# design.net
KiCad netlist of a schematic drawn in EasyEDA Pro
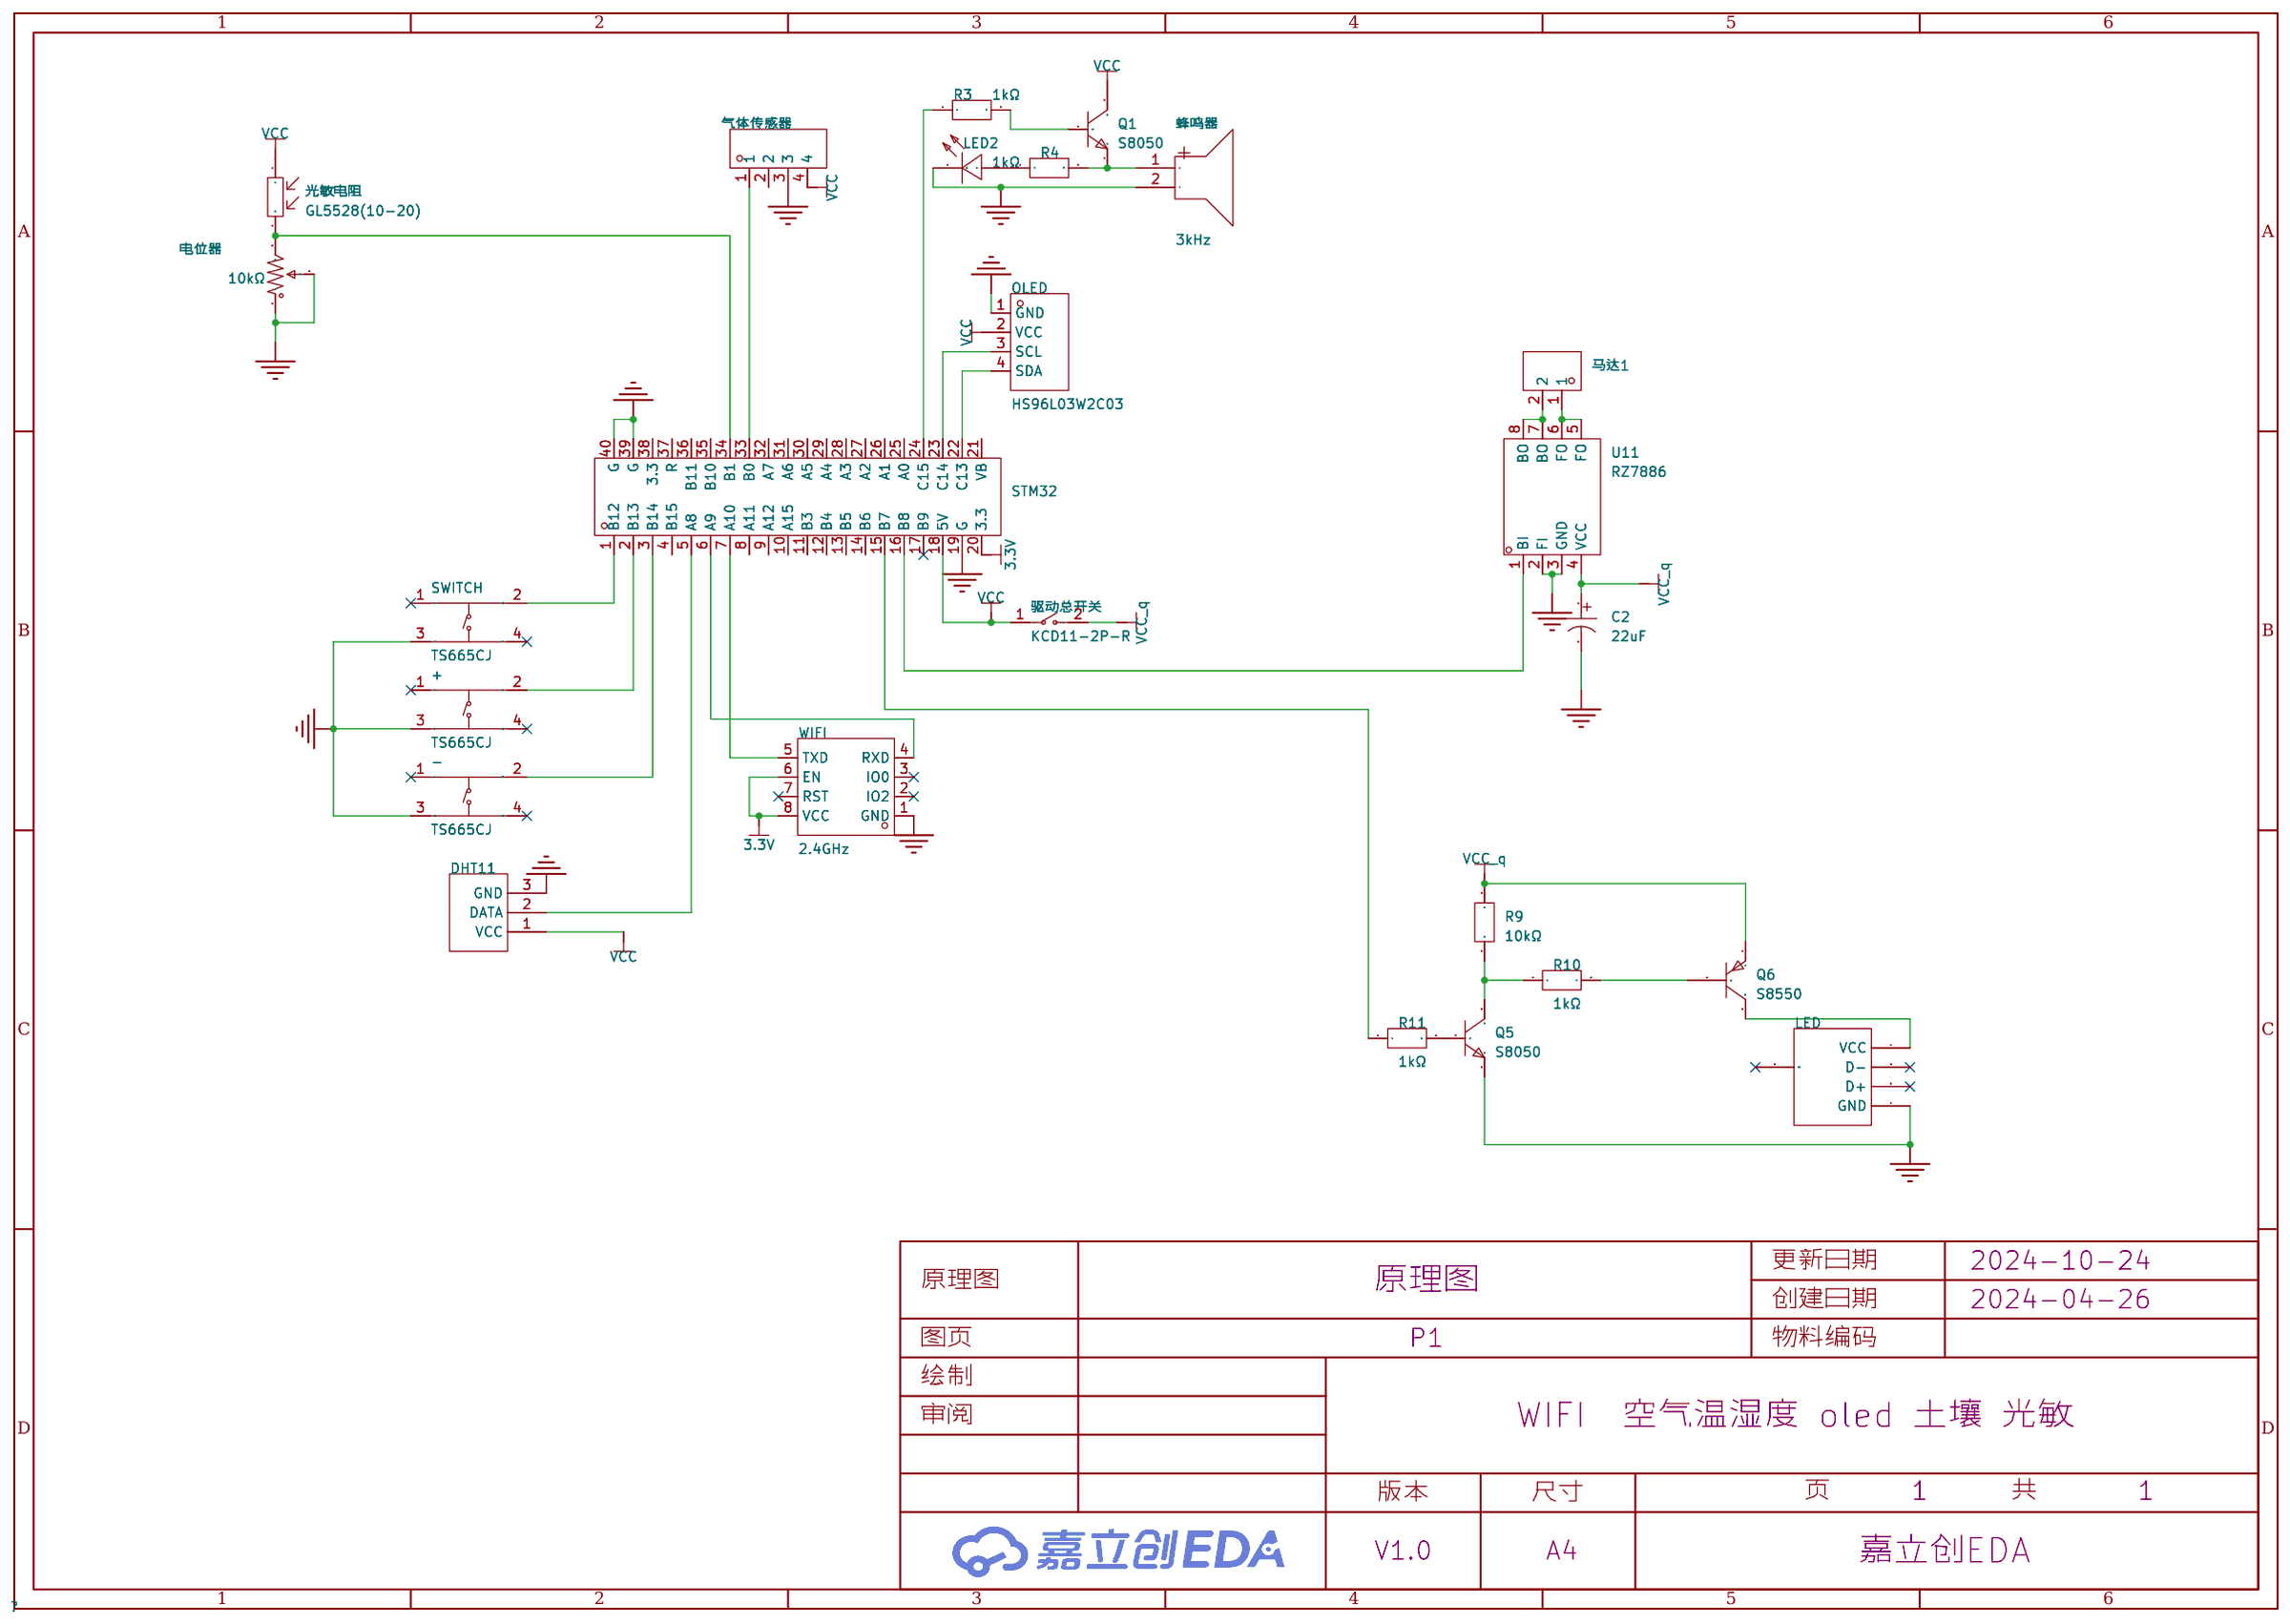
[diagram p0: schematic sheet]

(export (version "E")
  (design (tool "Eeschema 10.0.6"))
  (components
    (comp (ref "+")
      (value "TS665CJ")
      (footprint "easyedapro:SW-TH_4P-L6.0-W6.0-P4.50-LS6.5")
      (description "电路结构:单刀单掷;按钮形状:圆形按钮;安装方式:直插;开关长度:6mm;开关宽度:6mm;开关高度:5mm;触点电流:50mA;额定电压(DC):12V;带灯:-;机械寿命:-;")
      (fields (field (name "Manufacturer") "SHOU HAN(首韩)"))
      (libsource (lib "easyedapro") (part "TS665CJ"))
    )
    (comp (ref "-")
      (value "TS665CJ")
      (footprint "easyedapro:SW-TH_4P-L6.0-W6.0-P4.50-LS6.5")
      (description "电路结构:单刀单掷;按钮形状:圆形按钮;安装方式:直插;开关长度:6mm;开关宽度:6mm;开关高度:5mm;触点电流:50mA;额定电压(DC):12V;带灯:-;机械寿命:-;")
      (fields (field (name "Manufacturer") "SHOU HAN(首韩)"))
      (libsource (lib "easyedapro") (part "TS665CJ"))
    )
    (comp (ref "C2")
      (value "22uF")
      (footprint "easyedapro:CAP-TH_BD5.0-P2.00-D0.8-FD")
      (description "容值:22uF;精度:±20%;额定电压:50V;")
      (fields (field (name "Manufacturer Part") "KM220M050C110A") (field (name "Manufacturer") "CapXon(丰宾)"))
      (libsource (lib "easyedapro") (part "KM220M050C110A"))
    )
    (comp (ref "DHT11")
      (value "~")
      (footprint "easyedapro:HDR-M-2.54_1X3")
      (libsource (lib "easyedapro") (part "dht11模块"))
    )
    (comp (ref "LED")
      (value "AF 90° WJDG")
      (footprint "easyedapro:USB-A-TH_AF-WJDG")
      (description "连接器类型:Type-A;标准:USB 2.0;公母:母;端口数量:1;触点数量:4P;安装方式:弯插;额定电流 - 电源:1.5A;工作温度范围:-25°C~+85°C;")
      (fields (field (name "Manufacturer") "SHOU HAN(首韩)"))
      (libsource (lib "easyedapro") (part "AF 90° WJDG"))
    )
    (comp (ref "LED2")
      (value "204-10SDRD/S530-A3/F182-68")
      (footprint "easyedapro:LED-TH_BD4.0-P2.50-RD")
      (fields (field (name "Manufacturer") "EVERLIGHT(亿光)"))
      (libsource (lib "easyedapro") (part "204-10SDRD/S530-A3/F182-68"))
    )
    (comp (ref "OLED")
      (value "HS96L03W2C03")
      (footprint "easyedapro:OLED-TH_L27.8-W27.2-P2.54_C9900033791")
      (description "主控芯片:SSD1315;接口类型:I2C;尺寸(inch):0.96;像素分辨率:128x64;")
      (fields (field (name "Manufacturer") "HS(汉昇)"))
      (libsource (lib "easyedapro") (part "HS96L03W2C03"))
    )
    (comp (ref "Q1")
      (value "S8050")
      (footprint "easyedapro:TO-92-3_L4.5-W3.5-P1.27-L")
      (description "晶体管类型:NPN;集电极电流(Ic):500mA;集射极击穿电压(Vceo):25V;功率(Pd):625mW;直流电流增益(hFE@Ic,Vce):160@50mA,1V;")
      (fields (field (name "Manufacturer") "JSMSEMI(杰盛微)"))
      (libsource (lib "easyedapro") (part "S8050_C2931492"))
    )
    (comp (ref "Q5")
      (value "S8050")
      (footprint "easyedapro:TO-92-3_L4.5-W3.5-P1.27-L")
      (description "晶体管类型:NPN;集电极电流(Ic):500mA;集射极击穿电压(Vceo):25V;功率(Pd):625mW;直流电流增益(hFE@Ic,Vce):160@50mA,1V;")
      (fields (field (name "Manufacturer") "JSMSEMI(杰盛微)"))
      (libsource (lib "easyedapro") (part "S8050_C2931492"))
    )
    (comp (ref "Q6")
      (value "S8550")
      (footprint "easyedapro:TO-92-3_L4.5-W3.5-P1.27-L")
      (description "晶体管类型:PNP;集电极电流(Ic):500mA;集射极击穿电压(Vceo):25V;功率(Pd):625mW;直流电流增益(hFE@Ic,Vce):160@50mA,1V;")
      (fields (field (name "Manufacturer") "JSMSEMI(杰盛微)"))
      (libsource (lib "easyedapro") (part "s8550_c2931493"))
    )
    (comp (ref "R3")
      (value "1kΩ")
      (footprint "easyedapro:RES-TH_BD2.3-L6.5-P10.50-D0.5")
      (description "电阻类型:金属膜电阻;阻值:1kΩ;精度:±1%;功率:250mW;温度系数:±200ppm/°C;")
      (fields (field (name "Manufacturer Part") "MF1/4W-1KΩ±1%T52") (field (name "Manufacturer") "华星机电"))
      (libsource (lib "easyedapro") (part "MF1/4W-1KΩ±1%T52"))
    )
    (comp (ref "R4")
      (value "1kΩ")
      (footprint "easyedapro:RES-TH_BD2.3-L6.5-P10.50-D0.5")
      (description "电阻类型:金属膜电阻;阻值:1kΩ;精度:±1%;功率:250mW;温度系数:±200ppm/°C;")
      (fields (field (name "Manufacturer Part") "MF1/4W-1KΩ±1%T52") (field (name "Manufacturer") "华星机电"))
      (libsource (lib "easyedapro") (part "MF1/4W-1KΩ±1%T52"))
    )
    (comp (ref "R9")
      (value "10kΩ")
      (footprint "easyedapro:RES-TH_BD2.4-L6.3-P10.30-D0.6")
      (description "电阻类型:金属膜电阻;阻值:10kΩ;精度:±1%;功率:250mW;温度系数:±50ppm/°C;")
      (fields
        (field (name "Manufacturer Part") "RN1/4W10KFT/BA1")
        (field (name "Manufacturer") "Tyohm(幸亚电阻)")
      )
      (libsource (lib "easyedapro") (part "RN 1/4W 10K F T/B A1"))
    )
    (comp (ref "R10")
      (value "1kΩ")
      (footprint "easyedapro:RES-TH_BD2.3-L6.5-P10.50-D0.5")
      (description "电阻类型:金属膜电阻;阻值:1kΩ;精度:±1%;功率:250mW;温度系数:±200ppm/°C;")
      (fields (field (name "Manufacturer Part") "MF1/4W-1KΩ±1%T52") (field (name "Manufacturer") "华星机电"))
      (libsource (lib "easyedapro") (part "MF1/4W-1KΩ±1%T52"))
    )
    (comp (ref "R11")
      (value "1kΩ")
      (footprint "easyedapro:RES-TH_BD2.3-L6.5-P10.50-D0.5")
      (description "电阻类型:金属膜电阻;阻值:1kΩ;精度:±1%;功率:250mW;温度系数:±200ppm/°C;")
      (fields (field (name "Manufacturer Part") "MF1/4W-1KΩ±1%T52") (field (name "Manufacturer") "华星机电"))
      (libsource (lib "easyedapro") (part "MF1/4W-1KΩ±1%T52"))
    )
    (comp (ref "STM32")
      (value "~")
      (footprint "easyedapro:DIP-40_L50.8-W17.8-P2.54-LS15.2-BL")
      (libsource (lib "easyedapro") (part "stm32扩展板"))
    )
    (comp (ref "SWITCH")
      (value "TS665CJ")
      (footprint "easyedapro:SW-TH_4P-L6.0-W6.0-P4.50-LS6.5")
      (description "电路结构:单刀单掷;按钮形状:圆形按钮;安装方式:直插;开关长度:6mm;开关宽度:6mm;开关高度:5mm;触点电流:50mA;额定电压(DC):12V;带灯:-;机械寿命:-;")
      (fields (field (name "Manufacturer") "SHOU HAN(首韩)"))
      (libsource (lib "easyedapro") (part "TS665CJ"))
    )
    (comp (ref "U11")
      (value "RZ7886")
      (footprint "easyedapro:DIP-8_L10.0-W6.5-P2.54-LS7.6-BL")
      (description "马达驱动")
      (fields (field (name "Manufacturer") "RZ(睿智微)"))
      (libsource (lib "easyedapro") (part "RZ7886"))
    )
    (comp (ref "WIFI")
      (value "2.4GHz")
      (footprint "easyedapro:WIFIM-TH_8P-L24.7-W14.4-P2.54")
      (description "核心处理器:ESP8266芯片;频率:2.4GHz;天线形式:板载PCB天线;发射功率:16dBm;接收灵敏度:-90dBm;")
      (fields (field (name "Manufacturer Part") "ESP-01S") (field (name "Manufacturer") "Ai-Thinker(安信可)"))
      (libsource (lib "easyedapro") (part "ESP-01S_C503582"))
    )
    (comp (ref "光敏电阻")
      (value "GL5528(10-20)")
      (footprint "easyedapro:RES-TH_L5.1-W4.3-P3.40-D0.5")
      (description "暗电阻:1MΩ;亮电阻 @ 10Lux:10kΩ~20kΩ;光谱峰值(波长):540nm;")
      (fields (field (name "Manufacturer") "JCHL(晶创和立)"))
      (libsource (lib "easyedapro") (part "GL5528(10-20)"))
    )
    (comp (ref "气体传感器")
      (value "~")
      (footprint "easyedapro:HDR-TH_4P-P2.54-V-M")
      (libsource (lib "easyedapro") (part "PZ254V-11-04P"))
    )
    (comp (ref "电位器")
      (value "10kΩ")
      (footprint "easyedapro:RES-ADJ-TH_3362P")
      (description "阻值:10kΩ;精度:±10%;")
      (fields (field (name "Manufacturer Part") "3362P-1-103") (field (name "Manufacturer") "BOCHEN(博晨)"))
      (libsource (lib "easyedapro") (part "3362P-1-103_C118956"))
    )
    (comp (ref "蜂鸣器")
      (value "3kHz")
      (footprint "easyedapro:BUZ-TH_BD9.0-P5.00-D0.6-FD")
      (description "驱动方式:有源(内含驱动线路);构造类型:电磁式;频率:3kHz;声压(SPL):85dB@10cm;")
      (fields (field (name "Manufacturer Part") "HNB09A03") (field (name "Manufacturer") "华能"))
      (libsource (lib "easyedapro") (part "HNB09A03"))
    )
    (comp (ref "马达1")
      (value "MX126-5.0-02P-GN01-Cu-S-A")
      (footprint "easyedapro:CONN-TH_2P-P5.00_MX126-5.0-GN01-02P-CU-S-A")
      (fields (field (name "Manufacturer") "MAX(迈旭)"))
      (libsource (lib "easyedapro") (part "MX126-5.0-GN01-02P-CU-S-A"))
    )
    (comp (ref "驱动总开关")
      (value "KCD11-2P-R")
      (footprint "easyedapro:SW-TH_2P-L15.0-W10.5-P5.00_KCD11-2P-R")
      (description "带灯:无;引脚样式:焊片;额定电流:3A;额定电压(AC):250V;额定电压(DC):-;电路结构:单刀单掷;机械寿命:1万次;")
      (fields (field (name "Manufacturer") "SHOU HAN(首韩)"))
      (libsource (lib "easyedapro") (part "KCD11-2P-R"))
    )
  )
  (nets
    (net (code "1") (name "3.3V") (class "Default")
      (node (ref "STM32") (pin "20") (pinfunction "3.3_20") (pintype "input"))
      (node (ref "WIFI") (pin "6") (pinfunction "EN_6") (pintype "input"))
      (node (ref "WIFI") (pin "8") (pinfunction "VCC_8") (pintype "input"))
    )
    (net (code "2") (name "GND") (class "Default")
      (node (ref "+") (pin "3") (pinfunction "C_3") (pintype "unspecified"))
      (node (ref "-") (pin "3") (pinfunction "C_3") (pintype "unspecified"))
      (node (ref "C2") (pin "2") (pinfunction "2_2") (pintype "input"))
      (node (ref "DHT11") (pin "3") (pinfunction "GND_3") (pintype "input"))
      (node (ref "LED") (pin "4") (pinfunction "GND_4") (pintype "input"))
      (node (ref "LED2") (pin "1") (pinfunction "C_1") (pintype "unspecified"))
      (node (ref "OLED") (pin "1") (pinfunction "GND_1") (pintype "unspecified"))
      (node (ref "Q5") (pin "1") (pinfunction "E_1") (pintype "unspecified"))
      (node (ref "STM32") (pin "19") (pinfunction "G_19") (pintype "input"))
      (node (ref "STM32") (pin "39") (pinfunction "G_39") (pintype "input"))
      (node (ref "STM32") (pin "40") (pinfunction "G_40") (pintype "input"))
      (node (ref "SWITCH") (pin "3") (pinfunction "C_3") (pintype "unspecified"))
      (node (ref "U11") (pin "2") (pinfunction "FI_2") (pintype "unspecified"))
      (node (ref "U11") (pin "3") (pinfunction "GND_3") (pintype "unspecified"))
      (node (ref "WIFI") (pin "1") (pinfunction "GND_1") (pintype "input"))
      (node (ref "气体传感器") (pin "3") (pinfunction "3_3") (pintype "unspecified"))
      (node (ref "电位器") (pin "1") (pinfunction "1_1") (pintype "unspecified"))
      (node (ref "电位器") (pin "2") (pinfunction "2_2") (pintype "unspecified"))
      (node (ref "蜂鸣器") (pin "2") (pinfunction "-_2") (pintype "unspecified"))
    )
    (net (code "3") (name "Net-(+-B)") (class "Default")
      (node (ref "+") (pin "2") (pinfunction "B_2") (pintype "unspecified"))
      (node (ref "STM32") (pin "2") (pinfunction "B13_2") (pintype "input"))
    )
    (net (code "4") (name "Net-(--B)") (class "Default")
      (node (ref "-") (pin "2") (pinfunction "B_2") (pintype "unspecified"))
      (node (ref "STM32") (pin "3") (pinfunction "B14_3") (pintype "input"))
    )
    (net (code "5") (name "Net-(DHT11-DATA)") (class "Default")
      (node (ref "DHT11") (pin "2") (pinfunction "DATA_2") (pintype "input"))
      (node (ref "STM32") (pin "5") (pinfunction "A8_5") (pintype "input"))
    )
    (net (code "6") (name "Net-(LED-VCC)") (class "Default")
      (node (ref "LED") (pin "1") (pinfunction "VCC_1") (pintype "input"))
      (node (ref "Q6") (pin "3") (pinfunction "C_3") (pintype "unspecified"))
    )
    (net (code "7") (name "Net-(LED2-A)") (class "Default")
      (node (ref "LED2") (pin "2") (pinfunction "A_2") (pintype "unspecified"))
      (node (ref "R4") (pin "1") (pinfunction "1_1") (pintype "unspecified"))
    )
    (net (code "8") (name "Net-(OLED-SCL)") (class "Default")
      (node (ref "OLED") (pin "3") (pinfunction "SCL_3") (pintype "unspecified"))
      (node (ref "STM32") (pin "23") (pinfunction "C14_23") (pintype "input"))
    )
    (net (code "9") (name "Net-(OLED-SDA)") (class "Default")
      (node (ref "OLED") (pin "4") (pinfunction "SDA_4") (pintype "unspecified"))
      (node (ref "STM32") (pin "22") (pinfunction "C13_22") (pintype "input"))
    )
    (net (code "10") (name "Net-(Q1-B)") (class "Default")
      (node (ref "Q1") (pin "2") (pinfunction "B_2") (pintype "unspecified"))
      (node (ref "R3") (pin "2") (pinfunction "2_2") (pintype "unspecified"))
    )
    (net (code "11") (name "Net-(Q1-E)") (class "Default")
      (node (ref "Q1") (pin "1") (pinfunction "E_1") (pintype "unspecified"))
      (node (ref "R4") (pin "2") (pinfunction "2_2") (pintype "unspecified"))
      (node (ref "蜂鸣器") (pin "1") (pinfunction "+_1") (pintype "unspecified"))
    )
    (net (code "12") (name "Net-(Q5-B)") (class "Default")
      (node (ref "Q5") (pin "2") (pinfunction "B_2") (pintype "unspecified"))
      (node (ref "R11") (pin "2") (pinfunction "2_2") (pintype "unspecified"))
    )
    (net (code "13") (name "Net-(Q5-C)") (class "Default")
      (node (ref "Q5") (pin "3") (pinfunction "C_3") (pintype "unspecified"))
      (node (ref "R10") (pin "1") (pinfunction "1_1") (pintype "unspecified"))
      (node (ref "R9") (pin "1") (pinfunction "1_1") (pintype "unspecified"))
    )
    (net (code "14") (name "Net-(Q6-B)") (class "Default")
      (node (ref "Q6") (pin "2") (pinfunction "B_2") (pintype "unspecified"))
      (node (ref "R10") (pin "2") (pinfunction "2_2") (pintype "unspecified"))
    )
    (net (code "15") (name "Net-(STM32-A9)") (class "Default")
      (node (ref "STM32") (pin "6") (pinfunction "A9_6") (pintype "input"))
      (node (ref "WIFI") (pin "4") (pinfunction "RXD_4") (pintype "input"))
    )
    (net (code "16") (name "Net-(STM32-A10)") (class "Default")
      (node (ref "STM32") (pin "7") (pinfunction "A10_7") (pintype "input"))
      (node (ref "WIFI") (pin "5") (pinfunction "TXD_5") (pintype "input"))
    )
    (net (code "17") (name "Net-(STM32-B0)") (class "Default")
      (node (ref "STM32") (pin "33") (pinfunction "B0_33") (pintype "input"))
      (node (ref "气体传感器") (pin "1") (pinfunction "1_1") (pintype "unspecified"))
    )
    (net (code "18") (name "Net-(STM32-B1)") (class "Default")
      (node (ref "STM32") (pin "34") (pinfunction "B1_34") (pintype "input"))
      (node (ref "光敏电阻") (pin "2") (pinfunction "2_2") (pintype "input"))
      (node (ref "电位器") (pin "3") (pinfunction "3_3") (pintype "unspecified"))
    )
    (net (code "19") (name "Net-(STM32-B7)") (class "Default")
      (node (ref "R11") (pin "1") (pinfunction "1_1") (pintype "unspecified"))
      (node (ref "STM32") (pin "15") (pinfunction "B7_15") (pintype "input"))
    )
    (net (code "20") (name "Net-(STM32-B8)") (class "Default")
      (node (ref "STM32") (pin "16") (pinfunction "B8_16") (pintype "input"))
      (node (ref "U11") (pin "1") (pinfunction "BI_1") (pintype "unspecified"))
    )
    (net (code "21") (name "Net-(STM32-B12)") (class "Default")
      (node (ref "STM32") (pin "1") (pinfunction "B12_1") (pintype "input"))
      (node (ref "SWITCH") (pin "2") (pinfunction "B_2") (pintype "unspecified"))
    )
    (net (code "22") (name "Net-(STM32-C15)") (class "Default")
      (node (ref "R3") (pin "1") (pinfunction "1_1") (pintype "unspecified"))
      (node (ref "STM32") (pin "24") (pinfunction "C15_24") (pintype "input"))
    )
    (net (code "23") (name "Net-(U11-BO-Pad7)") (class "Default")
      (node (ref "U11") (pin "7") (pinfunction "BO_7") (pintype "unspecified"))
      (node (ref "U11") (pin "8") (pinfunction "BO_8") (pintype "unspecified"))
      (node (ref "马达1") (pin "2") (pinfunction "2_2") (pintype "unspecified"))
    )
    (net (code "24") (name "Net-(U11-FO-Pad5)") (class "Default")
      (node (ref "U11") (pin "5") (pinfunction "FO_5") (pintype "unspecified"))
      (node (ref "U11") (pin "6") (pinfunction "FO_6") (pintype "unspecified"))
      (node (ref "马达1") (pin "1") (pinfunction "1_1") (pintype "unspecified"))
    )
    (net (code "25") (name "VCC") (class "Default")
      (node (ref "DHT11") (pin "1") (pinfunction "VCC_1") (pintype "input"))
      (node (ref "OLED") (pin "2") (pinfunction "VCC_2") (pintype "unspecified"))
      (node (ref "Q1") (pin "3") (pinfunction "C_3") (pintype "unspecified"))
      (node (ref "STM32") (pin "18") (pinfunction "5V_18") (pintype "input"))
      (node (ref "光敏电阻") (pin "1") (pinfunction "1_1") (pintype "input"))
      (node (ref "气体传感器") (pin "4") (pinfunction "4_4") (pintype "unspecified"))
      (node (ref "驱动总开关") (pin "1") (pinfunction "1_1") (pintype "unspecified"))
    )
    (net (code "26") (name "VCC_q") (class "Default")
      (node (ref "C2") (pin "1") (pinfunction "1_1") (pintype "input"))
      (node (ref "Q6") (pin "1") (pinfunction "E_1") (pintype "unspecified"))
      (node (ref "R9") (pin "2") (pinfunction "2_2") (pintype "unspecified"))
      (node (ref "U11") (pin "4") (pinfunction "VCC_4") (pintype "unspecified"))
      (node (ref "驱动总开关") (pin "2") (pinfunction "2_2") (pintype "unspecified"))
    )
    (net (code "27") (name "unconnected-(+-A-Pad1)") (class "Default")
      (node (ref "+") (pin "1") (pinfunction "A_1") (pintype "unspecified+no_connect"))
    )
    (net (code "28") (name "unconnected-(+-D-Pad4)") (class "Default")
      (node (ref "+") (pin "4") (pinfunction "D_4") (pintype "unspecified+no_connect"))
    )
    (net (code "29") (name "unconnected-(--A-Pad1)") (class "Default")
      (node (ref "-") (pin "1") (pinfunction "A_1") (pintype "unspecified+no_connect"))
    )
    (net (code "30") (name "unconnected-(--D-Pad4)") (class "Default")
      (node (ref "-") (pin "4") (pinfunction "D_4") (pintype "unspecified+no_connect"))
    )
    (net (code "31") (name "unconnected-(LED-D+-Pad3)") (class "Default")
      (node (ref "LED") (pin "3") (pinfunction "D+_3") (pintype "input+no_connect"))
    )
    (net (code "32") (name "unconnected-(LED-D--Pad2)") (class "Default")
      (node (ref "LED") (pin "2") (pinfunction "D-_2") (pintype "input+no_connect"))
    )
    (net (code "33") (name "unconnected-(LED-SHLD-Pad5)") (class "Default")
      (node (ref "LED") (pin "5") (pinfunction "SHLD_5") (pintype "unspecified+no_connect"))
    )
    (net (code "34") (name "unconnected-(STM32-3.3-Pad38)") (class "Default")
      (node (ref "STM32") (pin "38") (pinfunction "3.3_38") (pintype "input"))
    )
    (net (code "35") (name "unconnected-(STM32-A0-Pad25)") (class "Default")
      (node (ref "STM32") (pin "25") (pinfunction "A0_25") (pintype "input"))
    )
    (net (code "36") (name "unconnected-(STM32-A1-Pad26)") (class "Default")
      (node (ref "STM32") (pin "26") (pinfunction "A1_26") (pintype "input"))
    )
    (net (code "37") (name "unconnected-(STM32-A2-Pad27)") (class "Default")
      (node (ref "STM32") (pin "27") (pinfunction "A2_27") (pintype "input"))
    )
    (net (code "38") (name "unconnected-(STM32-A3-Pad28)") (class "Default")
      (node (ref "STM32") (pin "28") (pinfunction "A3_28") (pintype "input"))
    )
    (net (code "39") (name "unconnected-(STM32-A4-Pad29)") (class "Default")
      (node (ref "STM32") (pin "29") (pinfunction "A4_29") (pintype "input"))
    )
    (net (code "40") (name "unconnected-(STM32-A5-Pad30)") (class "Default")
      (node (ref "STM32") (pin "30") (pinfunction "A5_30") (pintype "input"))
    )
    (net (code "41") (name "unconnected-(STM32-A6-Pad31)") (class "Default")
      (node (ref "STM32") (pin "31") (pinfunction "A6_31") (pintype "input"))
    )
    (net (code "42") (name "unconnected-(STM32-A7-Pad32)") (class "Default")
      (node (ref "STM32") (pin "32") (pinfunction "A7_32") (pintype "input"))
    )
    (net (code "43") (name "unconnected-(STM32-A11-Pad8)") (class "Default")
      (node (ref "STM32") (pin "8") (pinfunction "A11_8") (pintype "input"))
    )
    (net (code "44") (name "unconnected-(STM32-A12-Pad9)") (class "Default")
      (node (ref "STM32") (pin "9") (pinfunction "A12_9") (pintype "input"))
    )
    (net (code "45") (name "unconnected-(STM32-A15-Pad10)") (class "Default")
      (node (ref "STM32") (pin "10") (pinfunction "A15_10") (pintype "input"))
    )
    (net (code "46") (name "unconnected-(STM32-B3-Pad11)") (class "Default")
      (node (ref "STM32") (pin "11") (pinfunction "B3_11") (pintype "input"))
    )
    (net (code "47") (name "unconnected-(STM32-B4-Pad12)") (class "Default")
      (node (ref "STM32") (pin "12") (pinfunction "B4_12") (pintype "input"))
    )
    (net (code "48") (name "unconnected-(STM32-B5-Pad13)") (class "Default")
      (node (ref "STM32") (pin "13") (pinfunction "B5_13") (pintype "input"))
    )
    (net (code "49") (name "unconnected-(STM32-B6-Pad14)") (class "Default")
      (node (ref "STM32") (pin "14") (pinfunction "B6_14") (pintype "input"))
    )
    (net (code "50") (name "unconnected-(STM32-B9-Pad17)") (class "Default")
      (node (ref "STM32") (pin "17") (pinfunction "B9_17") (pintype "input+no_connect"))
    )
    (net (code "51") (name "unconnected-(STM32-B10-Pad35)") (class "Default")
      (node (ref "STM32") (pin "35") (pinfunction "B10_35") (pintype "input"))
    )
    (net (code "52") (name "unconnected-(STM32-B11-Pad36)") (class "Default")
      (node (ref "STM32") (pin "36") (pinfunction "B11_36") (pintype "input"))
    )
    (net (code "53") (name "unconnected-(STM32-B15-Pad4)") (class "Default")
      (node (ref "STM32") (pin "4") (pinfunction "B15_4") (pintype "input"))
    )
    (net (code "54") (name "unconnected-(STM32-R-Pad37)") (class "Default")
      (node (ref "STM32") (pin "37") (pinfunction "R_37") (pintype "input"))
    )
    (net (code "55") (name "unconnected-(STM32-VB-Pad21)") (class "Default")
      (node (ref "STM32") (pin "21") (pinfunction "VB_21") (pintype "input"))
    )
    (net (code "56") (name "unconnected-(SWITCH-A-Pad1)") (class "Default")
      (node (ref "SWITCH") (pin "1") (pinfunction "A_1") (pintype "unspecified+no_connect"))
    )
    (net (code "57") (name "unconnected-(SWITCH-D-Pad4)") (class "Default")
      (node (ref "SWITCH") (pin "4") (pinfunction "D_4") (pintype "unspecified+no_connect"))
    )
    (net (code "58") (name "unconnected-(WIFI-IO0-Pad3)") (class "Default")
      (node (ref "WIFI") (pin "3") (pinfunction "IO0_3") (pintype "input+no_connect"))
    )
    (net (code "59") (name "unconnected-(WIFI-IO2-Pad2)") (class "Default")
      (node (ref "WIFI") (pin "2") (pinfunction "IO2_2") (pintype "input+no_connect"))
    )
    (net (code "60") (name "unconnected-(WIFI-RST-Pad7)") (class "Default")
      (node (ref "WIFI") (pin "7") (pinfunction "RST_7") (pintype "input+no_connect"))
    )
    (net (code "61") (name "unconnected-(气体传感器-Pad2)") (class "Default")
      (node (ref "气体传感器") (pin "2") (pinfunction "2_2") (pintype "unspecified"))
    )
  )
)
